# SSRoof.net
KiCad netlist of a schematic drawn in Altium Designer
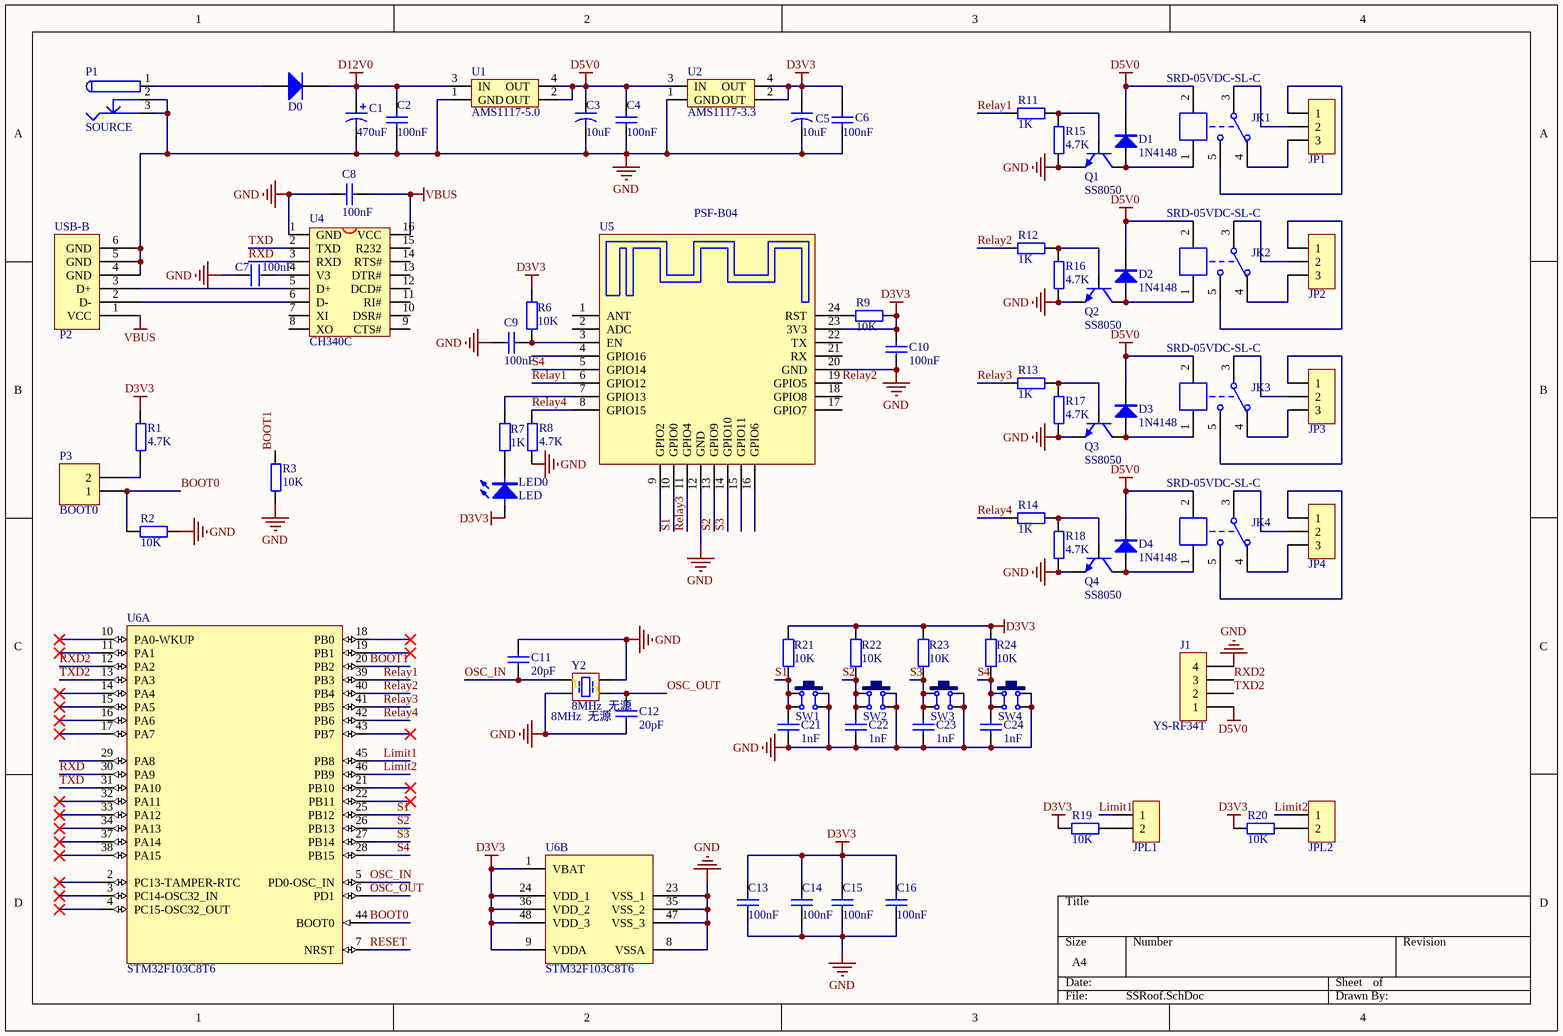
[diagram p0: SSRoof.SchDoc]

(export (version "E")
  (design (tool "Eeschema 10.0.6"))
  (components
    (comp (ref "C1")
      (value "470uF")
      (footprint "16V/470U(CD10X10D5)")
      (description "470UF      16V      CD10X10D5")
      (libsource (lib "平台原理图symbol图库V1.0") (part "C470UF016S"))
    )
    (comp (ref "C2")
      (value "100nF")
      (footprint "0603C")
      (description "Capacitor")
      (fields (field (name "PUBLISHER") "Altium Limited"))
      (libsource (lib "Crazy_PCB") (part "Cap"))
    )
    (comp (ref "C3")
      (value "10uF")
      (footprint "3216")
      (fields (field (name "VAULE") "10uF"))
      (libsource (lib "Crazy_PCB") (part "CAP2"))
    )
    (comp (ref "C4")
      (value "100nF")
      (footprint "0603C")
      (description "Capacitor")
      (fields (field (name "PUBLISHER") "Altium Limited"))
      (libsource (lib "Crazy_PCB") (part "Cap"))
    )
    (comp (ref "C5")
      (value "10uF")
      (footprint "3216")
      (fields (field (name "VAULE") "10uF"))
      (libsource (lib "Crazy_PCB") (part "CAP2"))
    )
    (comp (ref "C6")
      (value "100nF")
      (footprint "0603C")
      (description "Capacitor")
      (fields (field (name "PUBLISHER") "Altium Limited"))
      (libsource (lib "Crazy_PCB") (part "Cap"))
    )
    (comp (ref "C7")
      (value "100nF")
      (footprint "0603C")
      (libsource (lib "WarShip V3 STM32103封装库") (part "C"))
    )
    (comp (ref "C8")
      (value "100nF")
      (footprint "0603C")
      (description "Capacitor")
      (fields (field (name "PUBLISHER") "Altium Limited"))
      (libsource (lib "Crazy_PCB") (part "Cap"))
    )
    (comp (ref "C9")
      (value "100nF")
      (footprint "0603C")
      (description "Capacitor")
      (fields (field (name "PUBLISHER") "Altium Limited"))
      (libsource (lib "Crazy_PCB") (part "Cap"))
    )
    (comp (ref "C10")
      (value "100nF")
      (footprint "0603C")
      (description "Capacitor")
      (fields (field (name "PUBLISHER") "Altium Limited"))
      (libsource (lib "Crazy_PCB") (part "Cap"))
    )
    (comp (ref "C11")
      (value "20pF")
      (footprint "0603C")
      (description "Capacitor")
      (fields (field (name "PUBLISHER") "Altium Limited"))
      (libsource (lib "JL_SCH") (part "Cap"))
    )
    (comp (ref "C12")
      (value "20pF")
      (footprint "0603C")
      (description "Capacitor")
      (fields (field (name "PUBLISHER") "Altium Limited"))
      (libsource (lib "JL_SCH") (part "Cap"))
    )
    (comp (ref "C13")
      (value "100nF")
      (footprint "0603C")
      (description "Capacitor")
      (fields (field (name "PUBLISHER") "Altium Limited"))
      (libsource (lib "Crazy_PCB") (part "Cap"))
    )
    (comp (ref "C14")
      (value "100nF")
      (footprint "0603C")
      (description "Capacitor")
      (fields (field (name "PUBLISHER") "Altium Limited"))
      (libsource (lib "Crazy_PCB") (part "Cap"))
    )
    (comp (ref "C15")
      (value "100nF")
      (footprint "0603C")
      (description "Capacitor")
      (fields (field (name "PUBLISHER") "Altium Limited"))
      (libsource (lib "Crazy_PCB") (part "Cap"))
    )
    (comp (ref "C16")
      (value "100nF")
      (footprint "0603C")
      (description "Capacitor")
      (fields (field (name "PUBLISHER") "Altium Limited"))
      (libsource (lib "Crazy_PCB") (part "Cap"))
    )
    (comp (ref "C21")
      (value "1nF")
      (footprint "0603C")
      (description "Capacitor")
      (fields (field (name "PUBLISHER") "Altium Limited"))
      (libsource (lib "JL_SCH") (part "Cap"))
    )
    (comp (ref "C22")
      (value "1nF")
      (footprint "0603C")
      (description "Capacitor")
      (fields (field (name "PUBLISHER") "Altium Limited"))
      (libsource (lib "JL_SCH") (part "Cap"))
    )
    (comp (ref "C23")
      (value "1nF")
      (footprint "0603C")
      (description "Capacitor")
      (fields (field (name "PUBLISHER") "Altium Limited"))
      (libsource (lib "JL_SCH") (part "Cap"))
    )
    (comp (ref "C24")
      (value "1nF")
      (footprint "0603C")
      (description "Capacitor")
      (fields (field (name "PUBLISHER") "Altium Limited"))
      (libsource (lib "JL_SCH") (part "Cap"))
    )
    (comp (ref "D0")
      (value "M7")
      (footprint "DO-214AC")
      (description "High Conductance Fast Diode")
      (fields (field (name "PUBLISHER") "Altium Limited"))
      (libsource (lib "Crazy_PCB") (part "Diode"))
    )
    (comp (ref "D1")
      (value "1N4148")
      (footprint "SOD-323")
      (description "高速开关二极管")
      (fields (field (name "版权归属") "源创客"))
      (libsource (lib "8.1   - 二极管-整流桥") (part "1N4148"))
    )
    (comp (ref "D2")
      (value "1N4148")
      (footprint "SOD-323")
      (description "高速开关二极管")
      (fields (field (name "版权归属") "源创客"))
      (libsource (lib "8.1   - 二极管-整流桥") (part "1N4148"))
    )
    (comp (ref "D3")
      (value "1N4148")
      (footprint "SOD-323")
      (description "高速开关二极管")
      (fields (field (name "版权归属") "源创客"))
      (libsource (lib "8.1   - 二极管-整流桥") (part "1N4148"))
    )
    (comp (ref "D4")
      (value "1N4148")
      (footprint "SOD-323")
      (description "高速开关二极管")
      (fields (field (name "版权归属") "源创客"))
      (libsource (lib "8.1   - 二极管-整流桥") (part "1N4148"))
    )
    (comp (ref "J1")
      (value "YS-RF34T")
      (footprint "XH-4-SIDE")
      (description "Connector")
      (libsource (lib "General") (part "HDR1x4"))
    )
    (comp (ref "JK1")
      (value "SRD-05VDC-SL-C")
      (footprint "SRD-C_B")
      (description "5V一组转换")
      (fields (field (name "版权归属") "源创客"))
      (libsource (lib "7.1   - 继电器") (part "SRD-05VDC-SL-C"))
    )
    (comp (ref "JK2")
      (value "SRD-05VDC-SL-C")
      (footprint "SRD-C_B")
      (description "5V一组转换")
      (fields (field (name "版权归属") "源创客"))
      (libsource (lib "7.1   - 继电器") (part "SRD-05VDC-SL-C"))
    )
    (comp (ref "JK3")
      (value "SRD-05VDC-SL-C")
      (footprint "SRD-C_B")
      (description "5V一组转换")
      (fields (field (name "版权归属") "源创客"))
      (libsource (lib "7.1   - 继电器") (part "SRD-05VDC-SL-C"))
    )
    (comp (ref "JK4")
      (value "SRD-05VDC-SL-C")
      (footprint "SRD-C_B")
      (description "5V一组转换")
      (fields (field (name "版权归属") "源创客"))
      (libsource (lib "7.1   - 继电器") (part "SRD-05VDC-SL-C"))
    )
    (comp (ref "JP1")
      (value "HDR-1X3")
      (footprint "KF2EDGK5.0-LI-3P")
      (description "3P接插件")
      (fields (field (name "版权归属") "源创客"))
      (libsource (lib "4.9   - 接插件-脚距5.0") (part "Header 3"))
    )
    (comp (ref "JP2")
      (value "HDR-1X3")
      (footprint "KF2EDGK5.0-LI-3P")
      (description "3P接插件")
      (fields (field (name "版权归属") "源创客"))
      (libsource (lib "4.9   - 接插件-脚距5.0") (part "Header 3"))
    )
    (comp (ref "JP3")
      (value "HDR-1X3")
      (footprint "KF2EDGK5.0-LI-3P")
      (description "3P接插件")
      (fields (field (name "版权归属") "源创客"))
      (libsource (lib "4.9   - 接插件-脚距5.0") (part "Header 3"))
    )
    (comp (ref "JP4")
      (value "HDR-1X3")
      (footprint "KF2EDGK5.0-LI-3P")
      (description "3P接插件")
      (fields (field (name "版权归属") "源创客"))
      (libsource (lib "4.9   - 接插件-脚距5.0") (part "Header 3"))
    )
    (comp (ref "JPL1")
      (value "HDR-1X2")
      (footprint "KF2EDGK5.0-LI-2P")
      (description "2P接插件")
      (fields (field (name "版权归属") "源创客"))
      (libsource (lib "4.9   - 接插件-脚距5.0") (part "Header 2"))
    )
    (comp (ref "JPL2")
      (value "HDR-1X2")
      (footprint "KF2EDGK5.0-LI-2P")
      (description "2P接插件")
      (fields (field (name "版权归属") "源创客"))
      (libsource (lib "4.9   - 接插件-脚距5.0") (part "Header 2"))
    )
    (comp (ref "LED0") (value "LED") (footprint "LED-0603") (libsource (lib "General") (part "LED")))
    (comp (ref "P1")
      (value "SOURCE")
      (footprint "DC_5.5MM")
      (fields (field (name "PUBLISHER") "Altium Limited"))
      (libsource (lib "Crazy_PCB") (part "SOURCE"))
    )
    (comp (ref "P2") (value "USB-B") (footprint "USB-B") (libsource (lib "DX") (part "USB-B")))
    (comp (ref "P3")
      (value "BOOT0")
      (footprint "HDR1X2")
      (description "Header, 2-Pin")
      (fields (field (name "PUBLISHER") "Altium Limited"))
      (libsource (lib "Miscellaneous Connectors") (part "MHDR1X2"))
    )
    (comp (ref "Q1")
      (value "SS8050")
      (footprint "SOT23-3N")
      (description "高频放大-NPN型")
      (fields (field (name "版权归属") "源创客"))
      (libsource (lib "6.2   - 三极管") (part "8050-SMD"))
    )
    (comp (ref "Q2")
      (value "SS8050")
      (footprint "SOT23-3N")
      (description "高频放大-NPN型")
      (fields (field (name "版权归属") "源创客"))
      (libsource (lib "6.2   - 三极管") (part "8050-SMD"))
    )
    (comp (ref "Q3")
      (value "SS8050")
      (footprint "SOT23-3N")
      (description "高频放大-NPN型")
      (fields (field (name "版权归属") "源创客"))
      (libsource (lib "6.2   - 三极管") (part "8050-SMD"))
    )
    (comp (ref "Q4")
      (value "SS8050")
      (footprint "SOT23-3N")
      (description "高频放大-NPN型")
      (fields (field (name "版权归属") "源创客"))
      (libsource (lib "6.2   - 三极管") (part "8050-SMD"))
    )
    (comp (ref "R1") (value "4.7K") (footprint "0603R") (libsource (lib "WarShip V3 STM32103封装库") (part "R")))
    (comp (ref "R2")
      (value "10K")
      (footprint "0603R")
      (description "Resistor")
      (fields (field (name "PUBLISHER") "Altium Limited"))
      (libsource (lib "Crazy_PCB") (part "RES"))
    )
    (comp (ref "R3") (value "10K") (footprint "0603R") (libsource (lib "WarShip V3 STM32103封装库") (part "R")))
    (comp (ref "R6")
      (value "10K")
      (footprint "0603R")
      (description "Resistor")
      (fields (field (name "PUBLISHER") "Altium Limited"))
      (libsource (lib "") (part "RES_1"))
    )
    (comp (ref "R7")
      (value "1K")
      (footprint "0603R")
      (description "Resistor")
      (fields (field (name "PUBLISHER") "Altium Limited"))
      (libsource (lib "") (part "RES_3"))
    )
    (comp (ref "R8") (value "4.7K") (footprint "0603R") (libsource (lib "WarShip V3 STM32103封装库") (part "R")))
    (comp (ref "R9")
      (value "10K")
      (footprint "0603R")
      (description "Resistor")
      (fields (field (name "PUBLISHER") "Altium Limited"))
      (libsource (lib "Crazy_PCB") (part "RES"))
    )
    (comp (ref "R11")
      (value "1K")
      (footprint "0603R")
      (description "Resistor")
      (fields (field (name "PUBLISHER") "Altium Limited"))
      (libsource (lib "") (part "RES_2"))
    )
    (comp (ref "R12")
      (value "1K")
      (footprint "0603R")
      (description "Resistor")
      (fields (field (name "PUBLISHER") "Altium Limited"))
      (libsource (lib "") (part "RES_2"))
    )
    (comp (ref "R13")
      (value "1K")
      (footprint "0603R")
      (description "Resistor")
      (fields (field (name "PUBLISHER") "Altium Limited"))
      (libsource (lib "") (part "RES_2"))
    )
    (comp (ref "R14")
      (value "1K")
      (footprint "0603R")
      (description "Resistor")
      (fields (field (name "PUBLISHER") "Altium Limited"))
      (libsource (lib "") (part "RES_2"))
    )
    (comp (ref "R15")
      (value "4.7K")
      (footprint "0603R")
      (libsource (lib "WarShip V3 STM32103封装库") (part "R"))
    )
    (comp (ref "R16")
      (value "4.7K")
      (footprint "0603R")
      (libsource (lib "WarShip V3 STM32103封装库") (part "R"))
    )
    (comp (ref "R17")
      (value "4.7K")
      (footprint "0603R")
      (libsource (lib "WarShip V3 STM32103封装库") (part "R"))
    )
    (comp (ref "R18")
      (value "4.7K")
      (footprint "0603R")
      (libsource (lib "WarShip V3 STM32103封装库") (part "R"))
    )
    (comp (ref "R19")
      (value "10K")
      (footprint "0603R")
      (description "Resistor")
      (fields (field (name "PUBLISHER") "Altium Limited"))
      (libsource (lib "Crazy_PCB") (part "RES"))
    )
    (comp (ref "R20")
      (value "10K")
      (footprint "0603R")
      (description "Resistor")
      (fields (field (name "PUBLISHER") "Altium Limited"))
      (libsource (lib "Crazy_PCB") (part "RES"))
    )
    (comp (ref "R21")
      (value "10K")
      (footprint "0603R")
      (description "Resistor")
      (fields (field (name "PUBLISHER") "Altium Limited"))
      (libsource (lib "") (part "RES_1"))
    )
    (comp (ref "R22")
      (value "10K")
      (footprint "0603R")
      (description "Resistor")
      (fields (field (name "PUBLISHER") "Altium Limited"))
      (libsource (lib "") (part "RES_1"))
    )
    (comp (ref "R23")
      (value "10K")
      (footprint "0603R")
      (description "Resistor")
      (fields (field (name "PUBLISHER") "Altium Limited"))
      (libsource (lib "") (part "RES_1"))
    )
    (comp (ref "R24")
      (value "10K")
      (footprint "0603R")
      (description "Resistor")
      (fields (field (name "PUBLISHER") "Altium Limited"))
      (libsource (lib "") (part "RES_1"))
    )
    (comp (ref "SW1")
      (value "6x6x5")
      (footprint "TSW SMD-12*12*8")
      (description "贴片6x6轻触开关")
      (fields (field (name "版权归属") "源创客"))
      (libsource (lib "5.1   - 按键-开关") (part "TSW SMD-6x6"))
    )
    (comp (ref "SW2")
      (value "6x6x5")
      (footprint "TSW SMD-12*12*8")
      (description "贴片6x6轻触开关")
      (fields (field (name "版权归属") "源创客"))
      (libsource (lib "5.1   - 按键-开关") (part "TSW SMD-6x6"))
    )
    (comp (ref "SW3")
      (value "6x6x5")
      (footprint "TSW SMD-12*12*8")
      (description "贴片6x6轻触开关")
      (fields (field (name "版权归属") "源创客"))
      (libsource (lib "5.1   - 按键-开关") (part "TSW SMD-6x6"))
    )
    (comp (ref "SW4")
      (value "6x6x5")
      (footprint "TSW SMD-12*12*8")
      (description "贴片6x6轻触开关")
      (fields (field (name "版权归属") "源创客"))
      (libsource (lib "5.1   - 按键-开关") (part "TSW SMD-6x6"))
    )
    (comp (ref "U1")
      (value "AMS1117-5.0")
      (footprint "SOT223")
      (libsource (lib "MiniSTM32 V3.0封装库") (part "AMS1117"))
    )
    (comp (ref "U2")
      (value "AMS1117-3.3")
      (footprint "SOT223")
      (libsource (lib "MiniSTM32 V3.0封装库") (part "AMS1117"))
    )
    (comp (ref "U4")
      (value "CH340C")
      (footprint "SO-16")
      (description "USB2UART")
      (libsource (lib "WarShip V3 STM32103封装库") (part "CH340G"))
    )
    (comp (ref "U5") (value "PSF-B04") (libsource (lib "SS") (part "PSF-B04")))
    (comp (ref "U6")
      (value "STM32F103C8T6")
      (footprint "LQFP48_N")
      (libsource (lib "STMicroelectronics STM32 F1") (part "STM32F103C8T6"))
    )
    (comp (ref "Y2")
      (value "8MHz  无源")
      (footprint "X3225")
      (description "Crystal Oscillator")
      (fields (field (name "ALTIUM_VALUE") "8MHz  无源") (field (name "PUBLISHER") "Altium Limited"))
      (libsource (lib "JL_SCH") (part "XTAL_1"))
    )
  )
  (nets
    (net (code "1") (name "/BOOT0") (class "Default")
      (node (ref "P3") (pin "1") (pinfunction "1_1") (pintype "passive"))
      (node (ref "R2") (pin "1") (pinfunction "1_1") (pintype "passive"))
      (node (ref "U6") (pin "44") (pinfunction "BOOT0_44") (pintype "input"))
    )
    (net (code "2") (name "/BOOT1") (class "Default")
      (node (ref "R3") (pin "2") (pintype "passive"))
      (node (ref "U6") (pin "20") (pinfunction "PB2_20") (pintype "bidirectional"))
    )
    (net (code "3") (name "/Limit1") (class "Default")
      (node (ref "JPL1") (pin "1") (pinfunction "1_1") (pintype "passive"))
      (node (ref "U6") (pin "45") (pinfunction "PB8_45") (pintype "bidirectional"))
    )
    (net (code "4") (name "/Limit2") (class "Default")
      (node (ref "JPL2") (pin "1") (pinfunction "1_1") (pintype "passive"))
      (node (ref "U6") (pin "46") (pinfunction "PB9_46") (pintype "bidirectional"))
    )
    (net (code "5") (name "/OSC_IN") (class "Default")
      (node (ref "C11") (pin "1") (pinfunction "1_1") (pintype "passive"))
      (node (ref "U6") (pin "5") (pinfunction "PD0-OSC_IN_5") (pintype "bidirectional"))
      (node (ref "Y2") (pin "1") (pinfunction "OSC1_1") (pintype "passive"))
    )
    (net (code "6") (name "/OSC_OUT") (class "Default")
      (node (ref "C12") (pin "1") (pinfunction "1_1") (pintype "passive"))
      (node (ref "U6") (pin "6") (pinfunction "PD1_6") (pintype "bidirectional"))
      (node (ref "Y2") (pin "3") (pinfunction "OSC2_3") (pintype "passive"))
    )
    (net (code "7") (name "/RESET") (class "Default")
      (node (ref "U6") (pin "7") (pinfunction "NRST_7") (pintype "bidirectional"))
    )
    (net (code "8") (name "/RXD") (class "Default")
      (node (ref "U4") (pin "3") (pinfunction "RXD_3") (pintype "passive"))
      (node (ref "U6") (pin "30") (pinfunction "PA9_30") (pintype "bidirectional"))
    )
    (net (code "9") (name "/RXD2") (class "Default")
      (node (ref "J1") (pin "3") (pinfunction "3_3") (pintype "passive"))
      (node (ref "U6") (pin "12") (pinfunction "PA2_12") (pintype "bidirectional"))
    )
    (net (code "10") (name "/Relay1") (class "Default")
      (node (ref "R11") (pin "2") (pinfunction "2_2") (pintype "passive"))
      (node (ref "U5") (pin "6") (pinfunction "GPIO12_6") (pintype "passive"))
      (node (ref "U6") (pin "39") (pinfunction "PB3_39") (pintype "bidirectional"))
    )
    (net (code "11") (name "/Relay2") (class "Default")
      (node (ref "R12") (pin "2") (pinfunction "2_2") (pintype "passive"))
      (node (ref "U5") (pin "19") (pinfunction "GPIO5_19") (pintype "passive"))
      (node (ref "U6") (pin "40") (pinfunction "PB4_40") (pintype "bidirectional"))
    )
    (net (code "12") (name "/Relay3") (class "Default")
      (node (ref "R13") (pin "2") (pinfunction "2_2") (pintype "passive"))
      (node (ref "U5") (pin "11") (pinfunction "GPIO4_11") (pintype "passive"))
      (node (ref "U6") (pin "41") (pinfunction "PB5_41") (pintype "bidirectional"))
    )
    (net (code "13") (name "/Relay4") (class "Default")
      (node (ref "R14") (pin "2") (pinfunction "2_2") (pintype "passive"))
      (node (ref "R8") (pin "2") (pintype "passive"))
      (node (ref "U5") (pin "8") (pinfunction "GPIO15_8") (pintype "passive"))
      (node (ref "U6") (pin "42") (pinfunction "PB6_42") (pintype "bidirectional"))
    )
    (net (code "14") (name "/S1") (class "Default")
      (node (ref "C21") (pin "1") (pinfunction "1_1") (pintype "passive"))
      (node (ref "R21") (pin "1") (pinfunction "1_1") (pintype "passive"))
      (node (ref "SW1") (pin "1") (pinfunction "1_1") (pintype "passive"))
      (node (ref "SW1") (pin "4") (pinfunction "4_4") (pintype "passive"))
      (node (ref "U5") (pin "10") (pinfunction "GPIO0_10") (pintype "passive"))
      (node (ref "U6") (pin "25") (pinfunction "PB12_25") (pintype "bidirectional"))
    )
    (net (code "15") (name "/S2") (class "Default")
      (node (ref "C22") (pin "1") (pinfunction "1_1") (pintype "passive"))
      (node (ref "R22") (pin "1") (pinfunction "1_1") (pintype "passive"))
      (node (ref "SW2") (pin "1") (pinfunction "1_1") (pintype "passive"))
      (node (ref "SW2") (pin "4") (pinfunction "4_4") (pintype "passive"))
      (node (ref "U5") (pin "13") (pinfunction "GPIO9_13") (pintype "passive"))
      (node (ref "U6") (pin "26") (pinfunction "PB13_26") (pintype "bidirectional"))
    )
    (net (code "16") (name "/S3") (class "Default")
      (node (ref "C23") (pin "1") (pinfunction "1_1") (pintype "passive"))
      (node (ref "R23") (pin "1") (pinfunction "1_1") (pintype "passive"))
      (node (ref "SW3") (pin "1") (pinfunction "1_1") (pintype "passive"))
      (node (ref "SW3") (pin "4") (pinfunction "4_4") (pintype "passive"))
      (node (ref "U5") (pin "14") (pinfunction "GPIO10_14") (pintype "passive"))
      (node (ref "U6") (pin "27") (pinfunction "PB14_27") (pintype "bidirectional"))
    )
    (net (code "17") (name "/S4") (class "Default")
      (node (ref "C24") (pin "1") (pinfunction "1_1") (pintype "passive"))
      (node (ref "R24") (pin "1") (pinfunction "1_1") (pintype "passive"))
      (node (ref "SW4") (pin "1") (pinfunction "1_1") (pintype "passive"))
      (node (ref "SW4") (pin "4") (pinfunction "4_4") (pintype "passive"))
      (node (ref "U5") (pin "5") (pinfunction "GPIO14_5") (pintype "passive"))
      (node (ref "U6") (pin "28") (pinfunction "PB15_28") (pintype "bidirectional"))
    )
    (net (code "18") (name "/TXD") (class "Default")
      (node (ref "U4") (pin "2") (pinfunction "TXD_2") (pintype "passive"))
      (node (ref "U6") (pin "31") (pinfunction "PA10_31") (pintype "bidirectional"))
    )
    (net (code "19") (name "/TXD2") (class "Default")
      (node (ref "J1") (pin "2") (pinfunction "2_2") (pintype "passive"))
      (node (ref "U6") (pin "13") (pinfunction "PA3_13") (pintype "bidirectional"))
    )
    (net (code "20") (name "D3V3") (class "Default")
      (node (ref "C10") (pin "1") (pinfunction "1_1") (pintype "passive"))
      (node (ref "C13") (pin "2") (pinfunction "2_2") (pintype "passive"))
      (node (ref "C14") (pin "2") (pinfunction "2_2") (pintype "passive"))
      (node (ref "C15") (pin "2") (pinfunction "2_2") (pintype "passive"))
      (node (ref "C16") (pin "2") (pinfunction "2_2") (pintype "passive"))
      (node (ref "C5") (pin "1") (pinfunction "1_1") (pintype "passive"))
      (node (ref "C6") (pin "2") (pinfunction "2_2") (pintype "passive"))
      (node (ref "LED0") (pin "1") (pinfunction "A_1") (pintype "passive"))
      (node (ref "R1") (pin "2") (pintype "passive"))
      (node (ref "R19") (pin "1") (pinfunction "1_1") (pintype "passive"))
      (node (ref "R20") (pin "1") (pinfunction "1_1") (pintype "passive"))
      (node (ref "R21") (pin "2") (pinfunction "2_2") (pintype "passive"))
      (node (ref "R22") (pin "2") (pinfunction "2_2") (pintype "passive"))
      (node (ref "R23") (pin "2") (pinfunction "2_2") (pintype "passive"))
      (node (ref "R24") (pin "2") (pinfunction "2_2") (pintype "passive"))
      (node (ref "R6") (pin "2") (pinfunction "2_2") (pintype "passive"))
      (node (ref "R9") (pin "2") (pinfunction "2_2") (pintype "passive"))
      (node (ref "U2") (pin "2") (pinfunction "OUT_2") (pintype "passive"))
      (node (ref "U2") (pin "4") (pinfunction "OUT_4") (pintype "passive"))
      (node (ref "U5") (pin "23") (pinfunction "3V3_23") (pintype "passive"))
      (node (ref "U6") (pin "1") (pinfunction "VBAT_1") (pintype "power_in"))
      (node (ref "U6") (pin "24") (pinfunction "VDD_1_24") (pintype "power_in"))
      (node (ref "U6") (pin "36") (pinfunction "VDD_2_36") (pintype "power_in"))
      (node (ref "U6") (pin "48") (pinfunction "VDD_3_48") (pintype "power_in"))
      (node (ref "U6") (pin "9") (pinfunction "VDDA_9") (pintype "power_in"))
    )
    (net (code "21") (name "D5V0") (class "Default")
      (node (ref "C3") (pin "1") (pinfunction "1_1") (pintype "passive"))
      (node (ref "C4") (pin "2") (pinfunction "2_2") (pintype "passive"))
      (node (ref "D1") (pin "2") (pinfunction "K_2") (pintype "passive"))
      (node (ref "D2") (pin "2") (pinfunction "K_2") (pintype "passive"))
      (node (ref "D3") (pin "2") (pinfunction "K_2") (pintype "passive"))
      (node (ref "D4") (pin "2") (pinfunction "K_2") (pintype "passive"))
      (node (ref "J1") (pin "1") (pinfunction "1_1") (pintype "passive"))
      (node (ref "JK1") (pin "2") (pinfunction "2_2") (pintype "passive"))
      (node (ref "JK2") (pin "2") (pinfunction "2_2") (pintype "passive"))
      (node (ref "JK3") (pin "2") (pinfunction "2_2") (pintype "passive"))
      (node (ref "JK4") (pin "2") (pinfunction "2_2") (pintype "passive"))
      (node (ref "U1") (pin "2") (pinfunction "OUT_2") (pintype "passive"))
      (node (ref "U1") (pin "4") (pinfunction "OUT_4") (pintype "passive"))
      (node (ref "U2") (pin "3") (pinfunction "IN_3") (pintype "passive"))
    )
    (net (code "22") (name "D12V0") (class "Default")
      (node (ref "C1") (pin "1") (pinfunction "1_1") (pintype "passive"))
      (node (ref "C2") (pin "2") (pinfunction "2_2") (pintype "passive"))
      (node (ref "D0") (pin "2") (pinfunction "K_2") (pintype "passive"))
      (node (ref "U1") (pin "3") (pinfunction "IN_3") (pintype "passive"))
    )
    (net (code "23") (name "GND") (class "Default")
      (node (ref "C1") (pin "2") (pinfunction "2_2") (pintype "passive"))
      (node (ref "C10") (pin "2") (pinfunction "2_2") (pintype "passive"))
      (node (ref "C11") (pin "2") (pinfunction "2_2") (pintype "passive"))
      (node (ref "C12") (pin "2") (pinfunction "2_2") (pintype "passive"))
      (node (ref "C13") (pin "1") (pinfunction "1_1") (pintype "passive"))
      (node (ref "C14") (pin "1") (pinfunction "1_1") (pintype "passive"))
      (node (ref "C15") (pin "1") (pinfunction "1_1") (pintype "passive"))
      (node (ref "C16") (pin "1") (pinfunction "1_1") (pintype "passive"))
      (node (ref "C2") (pin "1") (pinfunction "1_1") (pintype "passive"))
      (node (ref "C21") (pin "2") (pinfunction "2_2") (pintype "passive"))
      (node (ref "C22") (pin "2") (pinfunction "2_2") (pintype "passive"))
      (node (ref "C23") (pin "2") (pinfunction "2_2") (pintype "passive"))
      (node (ref "C24") (pin "2") (pinfunction "2_2") (pintype "passive"))
      (node (ref "C3") (pin "2") (pinfunction "2_2") (pintype "passive"))
      (node (ref "C4") (pin "1") (pinfunction "1_1") (pintype "passive"))
      (node (ref "C5") (pin "2") (pinfunction "2_2") (pintype "passive"))
      (node (ref "C6") (pin "1") (pinfunction "1_1") (pintype "passive"))
      (node (ref "C7") (pin "1") (pintype "passive"))
      (node (ref "C8") (pin "1") (pinfunction "1_1") (pintype "passive"))
      (node (ref "C9") (pin "2") (pinfunction "2_2") (pintype "passive"))
      (node (ref "J1") (pin "4") (pinfunction "4_4") (pintype "passive"))
      (node (ref "P1") (pin "2") (pinfunction "2_2") (pintype "power_in"))
      (node (ref "P1") (pin "3") (pinfunction "3_3") (pintype "power_in"))
      (node (ref "P2") (pin "4") (pinfunction "GND_4") (pintype "passive"))
      (node (ref "P2") (pin "5") (pinfunction "GND_5") (pintype "passive"))
      (node (ref "P2") (pin "6") (pinfunction "GND_6") (pintype "passive"))
      (node (ref "Q1") (pin "2") (pinfunction "E_2") (pintype "passive"))
      (node (ref "Q2") (pin "2") (pinfunction "E_2") (pintype "passive"))
      (node (ref "Q3") (pin "2") (pinfunction "E_2") (pintype "passive"))
      (node (ref "Q4") (pin "2") (pinfunction "E_2") (pintype "passive"))
      (node (ref "R15") (pin "1") (pintype "passive"))
      (node (ref "R16") (pin "1") (pintype "passive"))
      (node (ref "R17") (pin "1") (pintype "passive"))
      (node (ref "R18") (pin "1") (pintype "passive"))
      (node (ref "R2") (pin "2") (pinfunction "2_2") (pintype "passive"))
      (node (ref "R3") (pin "1") (pintype "passive"))
      (node (ref "R8") (pin "1") (pintype "passive"))
      (node (ref "SW1") (pin "2") (pinfunction "2_2") (pintype "passive"))
      (node (ref "SW1") (pin "3") (pinfunction "3_3") (pintype "passive"))
      (node (ref "SW2") (pin "2") (pinfunction "2_2") (pintype "passive"))
      (node (ref "SW2") (pin "3") (pinfunction "3_3") (pintype "passive"))
      (node (ref "SW3") (pin "2") (pinfunction "2_2") (pintype "passive"))
      (node (ref "SW3") (pin "3") (pinfunction "3_3") (pintype "passive"))
      (node (ref "SW4") (pin "2") (pinfunction "2_2") (pintype "passive"))
      (node (ref "SW4") (pin "3") (pinfunction "3_3") (pintype "passive"))
      (node (ref "U1") (pin "1") (pinfunction "GND_1") (pintype "passive"))
      (node (ref "U2") (pin "1") (pinfunction "GND_1") (pintype "passive"))
      (node (ref "U4") (pin "1") (pinfunction "GND_1") (pintype "passive"))
      (node (ref "U5") (pin "12") (pinfunction "GND_12") (pintype "passive"))
      (node (ref "U5") (pin "20") (pinfunction "GND_20") (pintype "passive"))
      (node (ref "U6") (pin "23") (pinfunction "VSS_1_23") (pintype "power_in"))
      (node (ref "U6") (pin "35") (pinfunction "VSS_2_35") (pintype "power_in"))
      (node (ref "U6") (pin "47") (pinfunction "VSS_3_47") (pintype "power_in"))
      (node (ref "U6") (pin "8") (pinfunction "VSSA_8") (pintype "power_in"))
      (node (ref "Y2") (pin "2") (pinfunction "NA_2") (pintype "passive"))
      (node (ref "Y2") (pin "4") (pinfunction "NA_4") (pintype "passive"))
    )
    (net (code "24") (name "Net-(D0-A)") (class "Default")
      (node (ref "D0") (pin "1") (pinfunction "A_1") (pintype "passive"))
      (node (ref "P1") (pin "1") (pinfunction "1_1") (pintype "power_in"))
    )
    (net (code "25") (name "Net-(D1-A)") (class "Default")
      (node (ref "D1") (pin "1") (pinfunction "A_1") (pintype "passive"))
      (node (ref "JK1") (pin "1") (pinfunction "1_1") (pintype "passive"))
      (node (ref "Q1") (pin "3") (pinfunction "C_3") (pintype "passive"))
    )
    (net (code "26") (name "Net-(D2-A)") (class "Default")
      (node (ref "D2") (pin "1") (pinfunction "A_1") (pintype "passive"))
      (node (ref "JK2") (pin "1") (pinfunction "1_1") (pintype "passive"))
      (node (ref "Q2") (pin "3") (pinfunction "C_3") (pintype "passive"))
    )
    (net (code "27") (name "Net-(D3-A)") (class "Default")
      (node (ref "D3") (pin "1") (pinfunction "A_1") (pintype "passive"))
      (node (ref "JK3") (pin "1") (pinfunction "1_1") (pintype "passive"))
      (node (ref "Q3") (pin "3") (pinfunction "C_3") (pintype "passive"))
    )
    (net (code "28") (name "Net-(D4-A)") (class "Default")
      (node (ref "D4") (pin "1") (pinfunction "A_1") (pintype "passive"))
      (node (ref "JK4") (pin "1") (pinfunction "1_1") (pintype "passive"))
      (node (ref "Q4") (pin "3") (pinfunction "C_3") (pintype "passive"))
    )
    (net (code "29") (name "Net-(JK1-Pad3)") (class "Default")
      (node (ref "JK1") (pin "3") (pinfunction "3_3") (pintype "passive"))
      (node (ref "JP1") (pin "2") (pinfunction "2_2") (pintype "passive"))
    )
    (net (code "30") (name "Net-(JK1-Pad4)") (class "Default")
      (node (ref "JK1") (pin "4") (pinfunction "4_4") (pintype "passive"))
      (node (ref "JP1") (pin "3") (pinfunction "3_3") (pintype "passive"))
    )
    (net (code "31") (name "Net-(JK1-Pad5)") (class "Default")
      (node (ref "JK1") (pin "5") (pinfunction "5_5") (pintype "passive"))
      (node (ref "JP1") (pin "1") (pinfunction "1_1") (pintype "passive"))
    )
    (net (code "32") (name "Net-(JK2-Pad3)") (class "Default")
      (node (ref "JK2") (pin "3") (pinfunction "3_3") (pintype "passive"))
      (node (ref "JP2") (pin "2") (pinfunction "2_2") (pintype "passive"))
    )
    (net (code "33") (name "Net-(JK2-Pad4)") (class "Default")
      (node (ref "JK2") (pin "4") (pinfunction "4_4") (pintype "passive"))
      (node (ref "JP2") (pin "3") (pinfunction "3_3") (pintype "passive"))
    )
    (net (code "34") (name "Net-(JK2-Pad5)") (class "Default")
      (node (ref "JK2") (pin "5") (pinfunction "5_5") (pintype "passive"))
      (node (ref "JP2") (pin "1") (pinfunction "1_1") (pintype "passive"))
    )
    (net (code "35") (name "Net-(JK3-Pad3)") (class "Default")
      (node (ref "JK3") (pin "3") (pinfunction "3_3") (pintype "passive"))
      (node (ref "JP3") (pin "2") (pinfunction "2_2") (pintype "passive"))
    )
    (net (code "36") (name "Net-(JK3-Pad4)") (class "Default")
      (node (ref "JK3") (pin "4") (pinfunction "4_4") (pintype "passive"))
      (node (ref "JP3") (pin "3") (pinfunction "3_3") (pintype "passive"))
    )
    (net (code "37") (name "Net-(JK3-Pad5)") (class "Default")
      (node (ref "JK3") (pin "5") (pinfunction "5_5") (pintype "passive"))
      (node (ref "JP3") (pin "1") (pinfunction "1_1") (pintype "passive"))
    )
    (net (code "38") (name "Net-(JK4-Pad3)") (class "Default")
      (node (ref "JK4") (pin "3") (pinfunction "3_3") (pintype "passive"))
      (node (ref "JP4") (pin "2") (pinfunction "2_2") (pintype "passive"))
    )
    (net (code "39") (name "Net-(JK4-Pad4)") (class "Default")
      (node (ref "JK4") (pin "4") (pinfunction "4_4") (pintype "passive"))
      (node (ref "JP4") (pin "3") (pinfunction "3_3") (pintype "passive"))
    )
    (net (code "40") (name "Net-(JK4-Pad5)") (class "Default")
      (node (ref "JK4") (pin "5") (pinfunction "5_5") (pintype "passive"))
      (node (ref "JP4") (pin "1") (pinfunction "1_1") (pintype "passive"))
    )
    (net (code "41") (name "Net-(JPL1-Pad2)") (class "Default")
      (node (ref "JPL1") (pin "2") (pinfunction "2_2") (pintype "passive"))
      (node (ref "R19") (pin "2") (pinfunction "2_2") (pintype "passive"))
    )
    (net (code "42") (name "Net-(JPL2-Pad2)") (class "Default")
      (node (ref "JPL2") (pin "2") (pinfunction "2_2") (pintype "passive"))
      (node (ref "R20") (pin "2") (pinfunction "2_2") (pintype "passive"))
    )
    (net (code "43") (name "Net-(LED0-C)") (class "Default")
      (node (ref "LED0") (pin "2") (pinfunction "C_2") (pintype "passive"))
      (node (ref "R7") (pin "2") (pinfunction "2_2") (pintype "passive"))
    )
    (net (code "44") (name "Net-(P2-D+)") (class "Default")
      (node (ref "P2") (pin "3") (pinfunction "D+_3") (pintype "passive"))
      (node (ref "U4") (pin "5") (pinfunction "D+_5") (pintype "passive"))
    )
    (net (code "45") (name "Net-(P2-D-)") (class "Default")
      (node (ref "P2") (pin "2") (pinfunction "D-_2") (pintype "passive"))
      (node (ref "U4") (pin "6") (pinfunction "D-_6") (pintype "passive"))
    )
    (net (code "46") (name "Net-(P3-Pad2)") (class "Default")
      (node (ref "P3") (pin "2") (pinfunction "2_2") (pintype "passive"))
      (node (ref "R1") (pin "1") (pintype "passive"))
    )
    (net (code "47") (name "Net-(Q1-B)") (class "Default")
      (node (ref "Q1") (pin "1") (pinfunction "B_1") (pintype "passive"))
      (node (ref "R11") (pin "1") (pinfunction "1_1") (pintype "passive"))
      (node (ref "R15") (pin "2") (pintype "passive"))
    )
    (net (code "48") (name "Net-(Q2-B)") (class "Default")
      (node (ref "Q2") (pin "1") (pinfunction "B_1") (pintype "passive"))
      (node (ref "R12") (pin "1") (pinfunction "1_1") (pintype "passive"))
      (node (ref "R16") (pin "2") (pintype "passive"))
    )
    (net (code "49") (name "Net-(Q3-B)") (class "Default")
      (node (ref "Q3") (pin "1") (pinfunction "B_1") (pintype "passive"))
      (node (ref "R13") (pin "1") (pinfunction "1_1") (pintype "passive"))
      (node (ref "R17") (pin "2") (pintype "passive"))
    )
    (net (code "50") (name "Net-(Q4-B)") (class "Default")
      (node (ref "Q4") (pin "1") (pinfunction "B_1") (pintype "passive"))
      (node (ref "R14") (pin "1") (pinfunction "1_1") (pintype "passive"))
      (node (ref "R18") (pin "2") (pintype "passive"))
    )
    (net (code "51") (name "Net-(U4-V3)") (class "Default")
      (node (ref "C7") (pin "2") (pintype "passive"))
      (node (ref "U4") (pin "4") (pinfunction "V3_4") (pintype "passive"))
    )
    (net (code "52") (name "Net-(U5-EN)") (class "Default")
      (node (ref "C9") (pin "1") (pinfunction "1_1") (pintype "passive"))
      (node (ref "R6") (pin "1") (pinfunction "1_1") (pintype "passive"))
      (node (ref "U5") (pin "3") (pinfunction "EN_3") (pintype "passive"))
    )
    (net (code "53") (name "Net-(U5-GPIO13)") (class "Default")
      (node (ref "R7") (pin "1") (pinfunction "1_1") (pintype "passive"))
      (node (ref "U5") (pin "7") (pinfunction "GPIO13_7") (pintype "passive"))
    )
    (net (code "54") (name "Net-(U5-RST)") (class "Default")
      (node (ref "R9") (pin "1") (pinfunction "1_1") (pintype "passive"))
      (node (ref "U5") (pin "24") (pinfunction "RST_24") (pintype "passive"))
    )
    (net (code "55") (name "VBUS") (class "Default")
      (node (ref "C8") (pin "2") (pinfunction "2_2") (pintype "passive"))
      (node (ref "P2") (pin "1") (pinfunction "VCC_1") (pintype "passive"))
      (node (ref "U4") (pin "16") (pinfunction "VCC_16") (pintype "passive"))
    )
    (net (code "56") (name "unconnected-(U4-CTS#-Pad9)") (class "Default")
      (node (ref "U4") (pin "9") (pinfunction "CTS#_9") (pintype "passive"))
    )
    (net (code "57") (name "unconnected-(U4-DCD#-Pad12)") (class "Default")
      (node (ref "U4") (pin "12") (pinfunction "DCD#_12") (pintype "passive"))
    )
    (net (code "58") (name "unconnected-(U4-DSR#-Pad10)") (class "Default")
      (node (ref "U4") (pin "10") (pinfunction "DSR#_10") (pintype "passive"))
    )
    (net (code "59") (name "unconnected-(U4-DTR#-Pad13)") (class "Default")
      (node (ref "U4") (pin "13") (pinfunction "DTR#_13") (pintype "passive"))
    )
    (net (code "60") (name "unconnected-(U4-R232-Pad15)") (class "Default")
      (node (ref "U4") (pin "15") (pinfunction "R232_15") (pintype "passive"))
    )
    (net (code "61") (name "unconnected-(U4-RI#-Pad11)") (class "Default")
      (node (ref "U4") (pin "11") (pinfunction "RI#_11") (pintype "passive"))
    )
    (net (code "62") (name "unconnected-(U4-RTS#-Pad14)") (class "Default")
      (node (ref "U4") (pin "14") (pinfunction "RTS#_14") (pintype "passive"))
    )
    (net (code "63") (name "unconnected-(U4-XI-Pad7)") (class "Default")
      (node (ref "U4") (pin "7") (pinfunction "XI_7") (pintype "passive"))
    )
    (net (code "64") (name "unconnected-(U4-XO-Pad8)") (class "Default")
      (node (ref "U4") (pin "8") (pinfunction "XO_8") (pintype "passive"))
    )
    (net (code "65") (name "unconnected-(U5-ADC-Pad2)") (class "Default")
      (node (ref "U5") (pin "2") (pinfunction "ADC_2") (pintype "passive"))
    )
    (net (code "66") (name "unconnected-(U5-ANT-Pad1)") (class "Default")
      (node (ref "U5") (pin "1") (pinfunction "ANT_1") (pintype "passive"))
    )
    (net (code "67") (name "unconnected-(U5-GPIO2-Pad9)") (class "Default")
      (node (ref "U5") (pin "9") (pinfunction "GPIO2_9") (pintype "passive"))
    )
    (net (code "68") (name "unconnected-(U5-GPIO6-Pad16)") (class "Default")
      (node (ref "U5") (pin "16") (pinfunction "GPIO6_16") (pintype "passive"))
    )
    (net (code "69") (name "unconnected-(U5-GPIO7-Pad17)") (class "Default")
      (node (ref "U5") (pin "17") (pinfunction "GPIO7_17") (pintype "passive"))
    )
    (net (code "70") (name "unconnected-(U5-GPIO8-Pad18)") (class "Default")
      (node (ref "U5") (pin "18") (pinfunction "GPIO8_18") (pintype "passive"))
    )
    (net (code "71") (name "unconnected-(U5-GPIO11-Pad15)") (class "Default")
      (node (ref "U5") (pin "15") (pinfunction "GPIO11_15") (pintype "passive"))
    )
    (net (code "72") (name "unconnected-(U5-GPIO16-Pad4)") (class "Default")
      (node (ref "U5") (pin "4") (pinfunction "GPIO16_4") (pintype "passive"))
    )
    (net (code "73") (name "unconnected-(U5-RX-Pad21)") (class "Default")
      (node (ref "U5") (pin "21") (pinfunction "RX_21") (pintype "passive"))
    )
    (net (code "74") (name "unconnected-(U5-TX-Pad22)") (class "Default")
      (node (ref "U5") (pin "22") (pinfunction "TX_22") (pintype "passive"))
    )
    (net (code "75") (name "unconnected-(U6A-PA0-WKUP-Pad10)") (class "Default")
      (node (ref "U6") (pin "10") (pinfunction "PA0-WKUP_10") (pintype "bidirectional+no_connect"))
    )
    (net (code "76") (name "unconnected-(U6A-PA1-Pad11)") (class "Default")
      (node (ref "U6") (pin "11") (pinfunction "PA1_11") (pintype "bidirectional+no_connect"))
    )
    (net (code "77") (name "unconnected-(U6A-PA4-Pad14)") (class "Default")
      (node (ref "U6") (pin "14") (pinfunction "PA4_14") (pintype "bidirectional+no_connect"))
    )
    (net (code "78") (name "unconnected-(U6A-PA5-Pad15)") (class "Default")
      (node (ref "U6") (pin "15") (pinfunction "PA5_15") (pintype "bidirectional+no_connect"))
    )
    (net (code "79") (name "unconnected-(U6A-PA6-Pad16)") (class "Default")
      (node (ref "U6") (pin "16") (pinfunction "PA6_16") (pintype "bidirectional+no_connect"))
    )
    (net (code "80") (name "unconnected-(U6A-PA7-Pad17)") (class "Default")
      (node (ref "U6") (pin "17") (pinfunction "PA7_17") (pintype "bidirectional+no_connect"))
    )
    (net (code "81") (name "unconnected-(U6A-PA8-Pad29)") (class "Default")
      (node (ref "U6") (pin "29") (pinfunction "PA8_29") (pintype "bidirectional"))
    )
    (net (code "82") (name "unconnected-(U6A-PA11-Pad32)") (class "Default")
      (node (ref "U6") (pin "32") (pinfunction "PA11_32") (pintype "bidirectional+no_connect"))
    )
    (net (code "83") (name "unconnected-(U6A-PA12-Pad33)") (class "Default")
      (node (ref "U6") (pin "33") (pinfunction "PA12_33") (pintype "bidirectional+no_connect"))
    )
    (net (code "84") (name "unconnected-(U6A-PA13-Pad34)") (class "Default")
      (node (ref "U6") (pin "34") (pinfunction "PA13_34") (pintype "bidirectional+no_connect"))
    )
    (net (code "85") (name "unconnected-(U6A-PA14-Pad37)") (class "Default")
      (node (ref "U6") (pin "37") (pinfunction "PA14_37") (pintype "bidirectional+no_connect"))
    )
    (net (code "86") (name "unconnected-(U6A-PA15-Pad38)") (class "Default")
      (node (ref "U6") (pin "38") (pinfunction "PA15_38") (pintype "bidirectional+no_connect"))
    )
    (net (code "87") (name "unconnected-(U6A-PB0-Pad18)") (class "Default")
      (node (ref "U6") (pin "18") (pinfunction "PB0_18") (pintype "bidirectional+no_connect"))
    )
    (net (code "88") (name "unconnected-(U6A-PB1-Pad19)") (class "Default")
      (node (ref "U6") (pin "19") (pinfunction "PB1_19") (pintype "bidirectional+no_connect"))
    )
    (net (code "89") (name "unconnected-(U6A-PB7-Pad43)") (class "Default")
      (node (ref "U6") (pin "43") (pinfunction "PB7_43") (pintype "bidirectional+no_connect"))
    )
    (net (code "90") (name "unconnected-(U6A-PB10-Pad21)") (class "Default")
      (node (ref "U6") (pin "21") (pinfunction "PB10_21") (pintype "bidirectional+no_connect"))
    )
    (net (code "91") (name "unconnected-(U6A-PB11-Pad22)") (class "Default")
      (node (ref "U6") (pin "22") (pinfunction "PB11_22") (pintype "bidirectional+no_connect"))
    )
    (net (code "92") (name "unconnected-(U6A-PC13-TAMPER-RTC-Pad2)") (class "Default")
      (node (ref "U6") (pin "2") (pinfunction "PC13-TAMPER-RTC_2") (pintype "bidirectional+no_connect"))
    )
    (net (code "93") (name "unconnected-(U6A-PC14-OSC32_IN-Pad3)") (class "Default")
      (node (ref "U6") (pin "3") (pinfunction "PC14-OSC32_IN_3") (pintype "bidirectional+no_connect"))
    )
    (net (code "94") (name "unconnected-(U6A-PC15-OSC32_OUT-Pad4)") (class "Default")
      (node (ref "U6") (pin "4") (pinfunction "PC15-OSC32_OUT_4") (pintype "bidirectional+no_connect"))
    )
  )
)
